# Sheet2.net
KiCad netlist of a schematic drawn in Altium Designer
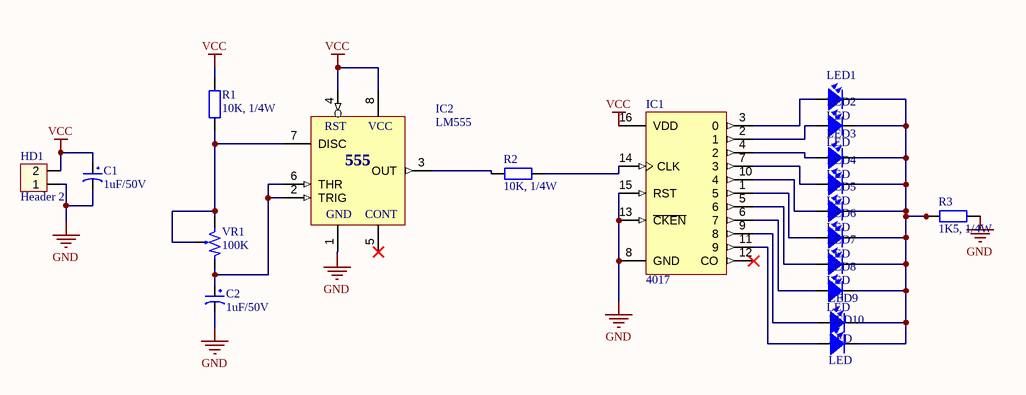
[diagram p0: Sheet2.SchDoc]

(export (version "E")
  (design (tool "Eeschema 10.0.6"))
  (components
    (comp (ref "C1")
      (value "1uF/50V")
      (footprint "CP1/2")
      (description "Cap P  0,1uF < 22uF , 16 - 50V")
      (libsource (lib "syhaunguyen") (part "CP1"))
    )
    (comp (ref "C2")
      (value "1uF/50V")
      (footprint "CP1/2")
      (description "Cap P  0,1uF < 22uF , 16 - 50V")
      (libsource (lib "syhaunguyen") (part "CP1"))
    )
    (comp (ref "HD1")
      (value "Header 2")
      (footprint "HED2")
      (description "Header 2 (Green)")
      (libsource (lib "syhaunguyen") (part "Hed2"))
    )
    (comp (ref "IC1")
      (value "4017")
      (footprint "DIP16/W0.3")
      (description "Decade Counter/Divider with 10 Decoded Outputs")
      (fields (field (name "DESIGNED BY") "VanDungEvn"))
      (libsource (lib "syhaunguyen") (part "4017"))
    )
    (comp (ref "IC2")
      (value "LM555")
      (footprint "DIP8/W0.3")
      (description "Timer")
      (libsource (lib "syhaunguyen") (part "LM555"))
    )
    (comp (ref "LED1")
      (value "LED")
      (footprint "LED-3")
      (description "LED Single colour Green and Red")
      (libsource (lib "syhaunguyen") (part "LED"))
    )
    (comp (ref "LED2")
      (value "LED")
      (footprint "LED-3")
      (description "LED Single colour Green and Red")
      (libsource (lib "syhaunguyen") (part "LED"))
    )
    (comp (ref "LED3")
      (value "LED")
      (footprint "LED-3")
      (description "LED Single colour Green and Red")
      (libsource (lib "syhaunguyen") (part "LED"))
    )
    (comp (ref "LED4")
      (value "LED")
      (footprint "LED-3")
      (description "LED Single colour Green and Red")
      (libsource (lib "syhaunguyen") (part "LED"))
    )
    (comp (ref "LED5")
      (value "LED")
      (footprint "LED-3")
      (description "LED Single colour Green and Red")
      (libsource (lib "syhaunguyen") (part "LED"))
    )
    (comp (ref "LED6")
      (value "LED")
      (footprint "LED-3")
      (description "LED Single colour Green and Red")
      (libsource (lib "syhaunguyen") (part "LED"))
    )
    (comp (ref "LED7")
      (value "LED")
      (footprint "LED-3")
      (description "LED Single colour Green and Red")
      (libsource (lib "syhaunguyen") (part "LED"))
    )
    (comp (ref "LED8")
      (value "LED")
      (footprint "LED-3")
      (description "LED Single colour Green and Red")
      (libsource (lib "syhaunguyen") (part "LED"))
    )
    (comp (ref "LED9")
      (value "LED")
      (footprint "LED-3")
      (description "LED Single colour Green and Red")
      (libsource (lib "syhaunguyen") (part "LED"))
    )
    (comp (ref "LED10")
      (value "LED")
      (footprint "LED-3")
      (description "LED Single colour Green and Red")
      (libsource (lib "syhaunguyen") (part "LED"))
    )
    (comp (ref "R1")
      (value "10K, 1/4W")
      (footprint "R1/4W")
      (description "Resistor 1/4W")
      (libsource (lib "syhaunguyen") (part "R1/4W"))
    )
    (comp (ref "R2")
      (value "10K, 1/4W")
      (footprint "R1/4W")
      (description "Resistor 1/4W")
      (libsource (lib "syhaunguyen") (part "R1/4W"))
    )
    (comp (ref "R3")
      (value "1K5, 1/4W")
      (footprint "R1/4W")
      (description "Resistor 1/4W")
      (libsource (lib "syhaunguyen") (part "R1/4W"))
    )
    (comp (ref "VR1")
      (value "100K")
      (footprint "VR")
      (description "Var Resistor")
      (libsource (lib "syhaunguyen") (part "VR1"))
    )
  )
  (nets
    (net (code "1") (name "GND") (class "Default")
      (node (ref "C1") (pin "2") (pinfunction "2_2") (pintype "passive"))
      (node (ref "C2") (pin "2") (pinfunction "2_2") (pintype "passive"))
      (node (ref "HD1") (pin "1") (pinfunction "1_1") (pintype "passive"))
      (node (ref "IC1") (pin "13") (pinfunction "~{CKEN}_13") (pintype "input"))
      (node (ref "IC1") (pin "15") (pinfunction "RST_15") (pintype "input"))
      (node (ref "IC1") (pin "8") (pinfunction "GND_8") (pintype "power_in"))
      (node (ref "IC2") (pin "1") (pinfunction "GND_1") (pintype "power_in"))
      (node (ref "R3") (pin "2") (pinfunction "2_2") (pintype "passive"))
    )
    (net (code "2") (name "Net-(IC1-0)") (class "Default")
      (node (ref "IC1") (pin "3") (pinfunction "0_3") (pintype "output"))
      (node (ref "LED1") (pin "1") (pinfunction "1_1") (pintype "passive"))
    )
    (net (code "3") (name "Net-(IC1-1)") (class "Default")
      (node (ref "IC1") (pin "2") (pinfunction "1_2") (pintype "output"))
      (node (ref "LED2") (pin "1") (pinfunction "1_1") (pintype "passive"))
    )
    (net (code "4") (name "Net-(IC1-2)") (class "Default")
      (node (ref "IC1") (pin "4") (pinfunction "2_4") (pintype "output"))
      (node (ref "LED3") (pin "1") (pinfunction "1_1") (pintype "passive"))
    )
    (net (code "5") (name "Net-(IC1-3)") (class "Default")
      (node (ref "IC1") (pin "7") (pinfunction "3_7") (pintype "output"))
      (node (ref "LED4") (pin "1") (pinfunction "1_1") (pintype "passive"))
    )
    (net (code "6") (name "Net-(IC1-4)") (class "Default")
      (node (ref "IC1") (pin "10") (pinfunction "4_10") (pintype "output"))
      (node (ref "LED5") (pin "1") (pinfunction "1_1") (pintype "passive"))
    )
    (net (code "7") (name "Net-(IC1-5)") (class "Default")
      (node (ref "IC1") (pin "1") (pinfunction "5_1") (pintype "output"))
      (node (ref "LED6") (pin "1") (pinfunction "1_1") (pintype "passive"))
    )
    (net (code "8") (name "Net-(IC1-6)") (class "Default")
      (node (ref "IC1") (pin "5") (pinfunction "6_5") (pintype "output"))
      (node (ref "LED7") (pin "1") (pinfunction "1_1") (pintype "passive"))
    )
    (net (code "9") (name "Net-(IC1-7)") (class "Default")
      (node (ref "IC1") (pin "6") (pinfunction "7_6") (pintype "output"))
      (node (ref "LED8") (pin "1") (pinfunction "1_1") (pintype "passive"))
    )
    (net (code "10") (name "Net-(IC1-8)") (class "Default")
      (node (ref "IC1") (pin "9") (pinfunction "8_9") (pintype "output"))
      (node (ref "LED9") (pin "1") (pinfunction "1_1") (pintype "passive"))
    )
    (net (code "11") (name "Net-(IC1-9)") (class "Default")
      (node (ref "IC1") (pin "11") (pinfunction "9_11") (pintype "output"))
      (node (ref "LED10") (pin "1") (pinfunction "1_1") (pintype "passive"))
    )
    (net (code "12") (name "Net-(IC1-CLK)") (class "Default")
      (node (ref "IC1") (pin "14") (pinfunction "CLK_14") (pintype "input"))
      (node (ref "R2") (pin "2") (pinfunction "2_2") (pintype "passive"))
    )
    (net (code "13") (name "Net-(IC2-DISC)") (class "Default")
      (node (ref "IC2") (pin "7") (pinfunction "DISC_7") (pintype "open_collector"))
      (node (ref "R1") (pin "1") (pinfunction "1_1") (pintype "passive"))
      (node (ref "VR1") (pin "2") (pinfunction "2_2") (pintype "passive"))
      (node (ref "VR1") (pin "3") (pinfunction "3_3") (pintype "passive"))
    )
    (net (code "14") (name "Net-(IC2-OUT)") (class "Default")
      (node (ref "IC2") (pin "3") (pinfunction "OUT_3") (pintype "output"))
      (node (ref "R2") (pin "1") (pinfunction "1_1") (pintype "passive"))
    )
    (net (code "15") (name "Net-(IC2-THR)") (class "Default")
      (node (ref "C2") (pin "1") (pinfunction "1_1") (pintype "passive"))
      (node (ref "IC2") (pin "2") (pinfunction "TRIG_2") (pintype "input"))
      (node (ref "IC2") (pin "6") (pinfunction "THR_6") (pintype "input"))
      (node (ref "VR1") (pin "1") (pinfunction "1_1") (pintype "passive"))
    )
    (net (code "16") (name "Net-(LED1-Pad2)") (class "Default")
      (node (ref "LED1") (pin "2") (pinfunction "2_2") (pintype "passive"))
      (node (ref "LED10") (pin "2") (pinfunction "2_2") (pintype "passive"))
      (node (ref "LED2") (pin "2") (pinfunction "2_2") (pintype "passive"))
      (node (ref "LED3") (pin "2") (pinfunction "2_2") (pintype "passive"))
      (node (ref "LED4") (pin "2") (pinfunction "2_2") (pintype "passive"))
      (node (ref "LED5") (pin "2") (pinfunction "2_2") (pintype "passive"))
      (node (ref "LED6") (pin "2") (pinfunction "2_2") (pintype "passive"))
      (node (ref "LED7") (pin "2") (pinfunction "2_2") (pintype "passive"))
      (node (ref "LED8") (pin "2") (pinfunction "2_2") (pintype "passive"))
      (node (ref "LED9") (pin "2") (pinfunction "2_2") (pintype "passive"))
      (node (ref "R3") (pin "1") (pinfunction "1_1") (pintype "passive"))
    )
    (net (code "17") (name "VCC") (class "Default")
      (node (ref "C1") (pin "1") (pinfunction "1_1") (pintype "passive"))
      (node (ref "HD1") (pin "2") (pinfunction "2_2") (pintype "passive"))
      (node (ref "IC1") (pin "16") (pinfunction "VDD_16") (pintype "power_in"))
      (node (ref "IC2") (pin "4") (pinfunction "RST_4") (pintype "input"))
      (node (ref "IC2") (pin "8") (pinfunction "VCC_8") (pintype "power_in"))
      (node (ref "R1") (pin "2") (pinfunction "2_2") (pintype "passive"))
    )
    (net (code "18") (name "unconnected-(IC1-CO-Pad12)") (class "Default")
      (node (ref "IC1") (pin "12") (pinfunction "CO_12") (pintype "output+no_connect"))
    )
    (net (code "19") (name "unconnected-(IC2-CONT-Pad5)") (class "Default")
      (node (ref "IC2") (pin "5") (pinfunction "CONT_5") (pintype "passive+no_connect"))
    )
  )
)
